# vireo.net
KiCad netlist of a schematic drawn in EAGLE
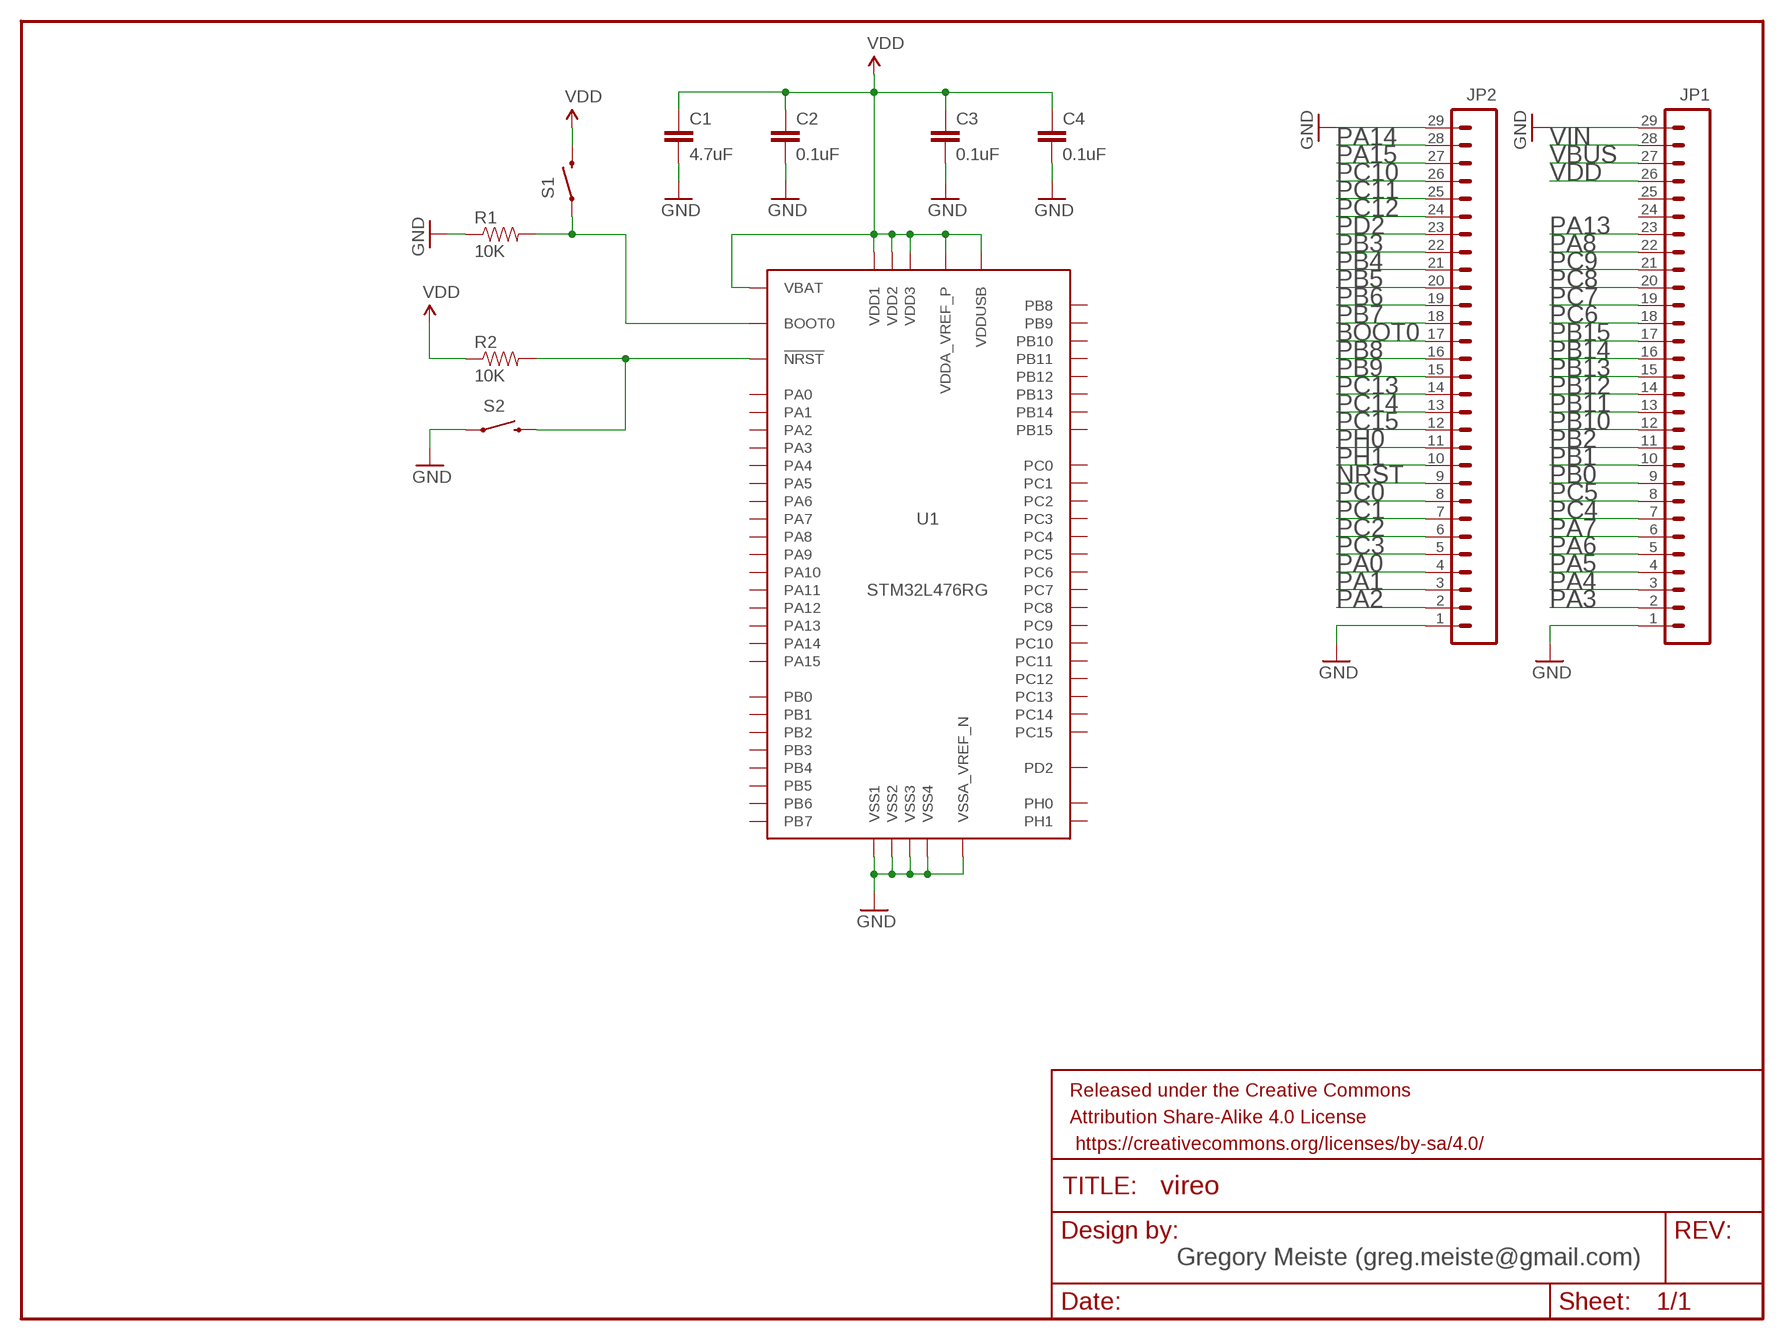
[diagram p0: schematic, sheet 1]

(export (version "E")
  (design (tool "Eeschema 10.0.6"))
  (components
    (comp (ref "C1")
      (value "4.7uF")
      (footprint "eagle-import:0603-CAP")
      (libsource (lib "eagle-import") (part "CAP0603-CAP"))
    )
    (comp (ref "C2")
      (value "0.1uF")
      (footprint "eagle-import:0603-CAP")
      (libsource (lib "eagle-import") (part "CAP0603-CAP"))
    )
    (comp (ref "C3")
      (value "0.1uF")
      (footprint "eagle-import:0603-CAP")
      (libsource (lib "eagle-import") (part "CAP0603-CAP"))
    )
    (comp (ref "C4")
      (value "0.1uF")
      (footprint "eagle-import:0603-CAP")
      (libsource (lib "eagle-import") (part "CAP0603-CAP"))
    )
    (comp (ref "FRAME1")
      (value "FRAME-LETTER")
      (footprint "eagle-import:CREATIVE_COMMONS")
      (libsource (lib "eagle-import") (part "FRAME-LETTER"))
    )
    (comp (ref "JP1")
      (value "M29NO_SILK")
      (footprint "eagle-import:1X29_NO_SILK")
      (libsource (lib "eagle-import") (part "M29NO_SILK"))
    )
    (comp (ref "JP2")
      (value "M29NO_SILK")
      (footprint "eagle-import:1X29_NO_SILK")
      (libsource (lib "eagle-import") (part "M29NO_SILK"))
    )
    (comp (ref "R1")
      (value "10K")
      (footprint "eagle-import:0603-RES")
      (libsource (lib "eagle-import") (part "RESISTOR0603-RES"))
    )
    (comp (ref "R2")
      (value "10K")
      (footprint "eagle-import:0603-RES")
      (libsource (lib "eagle-import") (part "RESISTOR0603-RES"))
    )
    (comp (ref "S1")
      (value "SWITCH-MOMENTARY-2SMD-3")
      (footprint "eagle-import:TACTILE_SWITCH_SMD-3")
      (libsource (lib "eagle-import") (part "SWITCH-MOMENTARY-2SMD-3"))
    )
    (comp (ref "S2")
      (value "SWITCH-MOMENTARY-2SMD-3")
      (footprint "eagle-import:TACTILE_SWITCH_SMD-3")
      (libsource (lib "eagle-import") (part "SWITCH-MOMENTARY-2SMD-3"))
    )
    (comp (ref "U1")
      (value "STM32L476RG")
      (footprint "eagle-import:LQFP64")
      (libsource (lib "eagle-import") (part "STM32L476RG"))
    )
  )
  (nets
    (net (code "1") (name "/BOOT0") (class "Default")
      (node (ref "JP2") (pin "17") (pinfunction "17_17") (pintype "passive"))
      (node (ref "R1") (pin "2") (pinfunction "2_2") (pintype "passive"))
      (node (ref "S1") (pin "1") (pinfunction "1_1") (pintype "passive"))
      (node (ref "U1") (pin "60") (pinfunction "BOOT0_60") (pintype "input"))
    )
    (net (code "2") (name "/NRST") (class "Default")
      (node (ref "JP2") (pin "9") (pinfunction "9_9") (pintype "passive"))
      (node (ref "R2") (pin "2") (pinfunction "2_2") (pintype "passive"))
      (node (ref "S2") (pin "4") (pinfunction "2_4") (pintype "passive"))
      (node (ref "U1") (pin "7") (pinfunction "~{NRST}_7") (pintype "input"))
    )
    (net (code "3") (name "/PA0") (class "Default")
      (node (ref "JP2") (pin "4") (pinfunction "4_4") (pintype "passive"))
    )
    (net (code "4") (name "/PA1") (class "Default")
      (node (ref "JP2") (pin "3") (pinfunction "3_3") (pintype "passive"))
    )
    (net (code "5") (name "/PA2") (class "Default")
      (node (ref "JP2") (pin "2") (pinfunction "2_2") (pintype "passive"))
    )
    (net (code "6") (name "/PA3") (class "Default")
      (node (ref "JP1") (pin "2") (pinfunction "2_2") (pintype "passive"))
    )
    (net (code "7") (name "/PA4") (class "Default")
      (node (ref "JP1") (pin "3") (pinfunction "3_3") (pintype "passive"))
    )
    (net (code "8") (name "/PA5") (class "Default")
      (node (ref "JP1") (pin "4") (pinfunction "4_4") (pintype "passive"))
    )
    (net (code "9") (name "/PA6") (class "Default")
      (node (ref "JP1") (pin "5") (pinfunction "5_5") (pintype "passive"))
    )
    (net (code "10") (name "/PA7") (class "Default")
      (node (ref "JP1") (pin "6") (pinfunction "6_6") (pintype "passive"))
    )
    (net (code "11") (name "/PA8") (class "Default")
      (node (ref "JP1") (pin "22") (pinfunction "22_22") (pintype "passive"))
    )
    (net (code "12") (name "/PA13") (class "Default")
      (node (ref "JP1") (pin "23") (pinfunction "23_23") (pintype "passive"))
    )
    (net (code "13") (name "/PA14") (class "Default")
      (node (ref "JP2") (pin "28") (pinfunction "28_28") (pintype "passive"))
    )
    (net (code "14") (name "/PA15") (class "Default")
      (node (ref "JP2") (pin "27") (pinfunction "27_27") (pintype "passive"))
    )
    (net (code "15") (name "/PB0") (class "Default")
      (node (ref "JP1") (pin "9") (pinfunction "9_9") (pintype "passive"))
    )
    (net (code "16") (name "/PB1") (class "Default")
      (node (ref "JP1") (pin "10") (pinfunction "10_10") (pintype "passive"))
    )
    (net (code "17") (name "/PB2") (class "Default")
      (node (ref "JP1") (pin "11") (pinfunction "11_11") (pintype "passive"))
    )
    (net (code "18") (name "/PB3") (class "Default")
      (node (ref "JP2") (pin "22") (pinfunction "22_22") (pintype "passive"))
    )
    (net (code "19") (name "/PB4") (class "Default")
      (node (ref "JP2") (pin "21") (pinfunction "21_21") (pintype "passive"))
    )
    (net (code "20") (name "/PB5") (class "Default")
      (node (ref "JP2") (pin "20") (pinfunction "20_20") (pintype "passive"))
    )
    (net (code "21") (name "/PB6") (class "Default")
      (node (ref "JP2") (pin "19") (pinfunction "19_19") (pintype "passive"))
    )
    (net (code "22") (name "/PB7") (class "Default")
      (node (ref "JP2") (pin "18") (pinfunction "18_18") (pintype "passive"))
    )
    (net (code "23") (name "/PB8") (class "Default")
      (node (ref "JP2") (pin "16") (pinfunction "16_16") (pintype "passive"))
    )
    (net (code "24") (name "/PB9") (class "Default")
      (node (ref "JP2") (pin "15") (pinfunction "15_15") (pintype "passive"))
    )
    (net (code "25") (name "/PB10") (class "Default")
      (node (ref "JP1") (pin "12") (pinfunction "12_12") (pintype "passive"))
    )
    (net (code "26") (name "/PB11") (class "Default")
      (node (ref "JP1") (pin "13") (pinfunction "13_13") (pintype "passive"))
    )
    (net (code "27") (name "/PB12") (class "Default")
      (node (ref "JP1") (pin "14") (pinfunction "14_14") (pintype "passive"))
    )
    (net (code "28") (name "/PB13") (class "Default")
      (node (ref "JP1") (pin "15") (pinfunction "15_15") (pintype "passive"))
    )
    (net (code "29") (name "/PB14") (class "Default")
      (node (ref "JP1") (pin "16") (pinfunction "16_16") (pintype "passive"))
    )
    (net (code "30") (name "/PB15") (class "Default")
      (node (ref "JP1") (pin "17") (pinfunction "17_17") (pintype "passive"))
    )
    (net (code "31") (name "/PC0") (class "Default")
      (node (ref "JP2") (pin "8") (pinfunction "8_8") (pintype "passive"))
    )
    (net (code "32") (name "/PC1") (class "Default")
      (node (ref "JP2") (pin "7") (pinfunction "7_7") (pintype "passive"))
    )
    (net (code "33") (name "/PC2") (class "Default")
      (node (ref "JP2") (pin "6") (pinfunction "6_6") (pintype "passive"))
    )
    (net (code "34") (name "/PC3") (class "Default")
      (node (ref "JP2") (pin "5") (pinfunction "5_5") (pintype "passive"))
    )
    (net (code "35") (name "/PC4") (class "Default")
      (node (ref "JP1") (pin "7") (pinfunction "7_7") (pintype "passive"))
    )
    (net (code "36") (name "/PC5") (class "Default")
      (node (ref "JP1") (pin "8") (pinfunction "8_8") (pintype "passive"))
    )
    (net (code "37") (name "/PC6") (class "Default")
      (node (ref "JP1") (pin "18") (pinfunction "18_18") (pintype "passive"))
    )
    (net (code "38") (name "/PC7") (class "Default")
      (node (ref "JP1") (pin "19") (pinfunction "19_19") (pintype "passive"))
    )
    (net (code "39") (name "/PC8") (class "Default")
      (node (ref "JP1") (pin "20") (pinfunction "20_20") (pintype "passive"))
    )
    (net (code "40") (name "/PC9") (class "Default")
      (node (ref "JP1") (pin "21") (pinfunction "21_21") (pintype "passive"))
    )
    (net (code "41") (name "/PC10") (class "Default")
      (node (ref "JP2") (pin "26") (pinfunction "26_26") (pintype "passive"))
    )
    (net (code "42") (name "/PC11") (class "Default")
      (node (ref "JP2") (pin "25") (pinfunction "25_25") (pintype "passive"))
    )
    (net (code "43") (name "/PC12") (class "Default")
      (node (ref "JP2") (pin "24") (pinfunction "24_24") (pintype "passive"))
    )
    (net (code "44") (name "/PC13") (class "Default")
      (node (ref "JP2") (pin "14") (pinfunction "14_14") (pintype "passive"))
    )
    (net (code "45") (name "/PC14") (class "Default")
      (node (ref "JP2") (pin "13") (pinfunction "13_13") (pintype "passive"))
    )
    (net (code "46") (name "/PC15") (class "Default")
      (node (ref "JP2") (pin "12") (pinfunction "12_12") (pintype "passive"))
    )
    (net (code "47") (name "/PD2") (class "Default")
      (node (ref "JP2") (pin "23") (pinfunction "23_23") (pintype "passive"))
    )
    (net (code "48") (name "/PH0") (class "Default")
      (node (ref "JP2") (pin "11") (pinfunction "11_11") (pintype "passive"))
    )
    (net (code "49") (name "/PH1") (class "Default")
      (node (ref "JP2") (pin "10") (pinfunction "10_10") (pintype "passive"))
    )
    (net (code "50") (name "/VBUS") (class "Default")
      (node (ref "JP1") (pin "27") (pinfunction "27_27") (pintype "passive"))
    )
    (net (code "51") (name "/VIN") (class "Default")
      (node (ref "JP1") (pin "28") (pinfunction "28_28") (pintype "passive"))
    )
    (net (code "52") (name "GND") (class "Default")
      (node (ref "C1") (pin "2") (pinfunction "2_2") (pintype "passive"))
      (node (ref "C2") (pin "2") (pinfunction "2_2") (pintype "passive"))
      (node (ref "C3") (pin "2") (pinfunction "2_2") (pintype "passive"))
      (node (ref "C4") (pin "2") (pinfunction "2_2") (pintype "passive"))
      (node (ref "JP1") (pin "1") (pinfunction "1_1") (pintype "passive"))
      (node (ref "JP1") (pin "29") (pinfunction "29_29") (pintype "passive"))
      (node (ref "JP2") (pin "1") (pinfunction "1_1") (pintype "passive"))
      (node (ref "JP2") (pin "29") (pinfunction "29_29") (pintype "passive"))
      (node (ref "R1") (pin "1") (pinfunction "1_1") (pintype "passive"))
      (node (ref "S2") (pin "1") (pinfunction "1_1") (pintype "passive"))
      (node (ref "U1") (pin "12") (pinfunction "VSSA_VREF_N_12") (pintype "power_in"))
      (node (ref "U1") (pin "18") (pinfunction "VSS1_18") (pintype "power_in"))
      (node (ref "U1") (pin "31") (pinfunction "VSS2_31") (pintype "power_in"))
      (node (ref "U1") (pin "47") (pinfunction "VSS3_47") (pintype "power_in"))
      (node (ref "U1") (pin "63") (pinfunction "VSS4_63") (pintype "power_in"))
    )
    (net (code "53") (name "VDD") (class "Default")
      (node (ref "C1") (pin "1") (pinfunction "1_1") (pintype "passive"))
      (node (ref "C2") (pin "1") (pinfunction "1_1") (pintype "passive"))
      (node (ref "C3") (pin "1") (pinfunction "1_1") (pintype "passive"))
      (node (ref "C4") (pin "1") (pinfunction "1_1") (pintype "passive"))
      (node (ref "JP1") (pin "26") (pinfunction "26_26") (pintype "passive"))
      (node (ref "R2") (pin "1") (pinfunction "1_1") (pintype "passive"))
      (node (ref "S1") (pin "4") (pinfunction "2_4") (pintype "passive"))
      (node (ref "U1") (pin "1") (pinfunction "VBAT_1") (pintype "power_in"))
      (node (ref "U1") (pin "13") (pinfunction "VDDA_VREF_P_13") (pintype "power_in"))
      (node (ref "U1") (pin "19") (pinfunction "VDD1_19") (pintype "power_in"))
      (node (ref "U1") (pin "32") (pinfunction "VDD2_32") (pintype "power_in"))
      (node (ref "U1") (pin "48") (pinfunction "VDDUSB_48") (pintype "power_in"))
      (node (ref "U1") (pin "64") (pinfunction "VDD3_64") (pintype "power_in"))
    )
    (net (code "54") (name "unconnected-(JP1-Pad24)") (class "Default")
      (node (ref "JP1") (pin "24") (pinfunction "24_24") (pintype "passive"))
    )
    (net (code "55") (name "unconnected-(JP1-Pad25)") (class "Default")
      (node (ref "JP1") (pin "25") (pinfunction "25_25") (pintype "passive"))
    )
    (net (code "56") (name "unconnected-(U1-PA0-Pad14)") (class "Default")
      (node (ref "U1") (pin "14") (pinfunction "PA0_14") (pintype "bidirectional"))
    )
    (net (code "57") (name "unconnected-(U1-PA1-Pad15)") (class "Default")
      (node (ref "U1") (pin "15") (pinfunction "PA1_15") (pintype "bidirectional"))
    )
    (net (code "58") (name "unconnected-(U1-PA2-Pad16)") (class "Default")
      (node (ref "U1") (pin "16") (pinfunction "PA2_16") (pintype "bidirectional"))
    )
    (net (code "59") (name "unconnected-(U1-PA3-Pad17)") (class "Default")
      (node (ref "U1") (pin "17") (pinfunction "PA3_17") (pintype "bidirectional"))
    )
    (net (code "60") (name "unconnected-(U1-PA4-Pad20)") (class "Default")
      (node (ref "U1") (pin "20") (pinfunction "PA4_20") (pintype "bidirectional"))
    )
    (net (code "61") (name "unconnected-(U1-PA5-Pad21)") (class "Default")
      (node (ref "U1") (pin "21") (pinfunction "PA5_21") (pintype "bidirectional"))
    )
    (net (code "62") (name "unconnected-(U1-PA6-Pad22)") (class "Default")
      (node (ref "U1") (pin "22") (pinfunction "PA6_22") (pintype "bidirectional"))
    )
    (net (code "63") (name "unconnected-(U1-PA7-Pad23)") (class "Default")
      (node (ref "U1") (pin "23") (pinfunction "PA7_23") (pintype "bidirectional"))
    )
    (net (code "64") (name "unconnected-(U1-PA8-Pad41)") (class "Default")
      (node (ref "U1") (pin "41") (pinfunction "PA8_41") (pintype "bidirectional"))
    )
    (net (code "65") (name "unconnected-(U1-PA9-Pad42)") (class "Default")
      (node (ref "U1") (pin "42") (pinfunction "PA9_42") (pintype "bidirectional"))
    )
    (net (code "66") (name "unconnected-(U1-PA10-Pad43)") (class "Default")
      (node (ref "U1") (pin "43") (pinfunction "PA10_43") (pintype "bidirectional"))
    )
    (net (code "67") (name "unconnected-(U1-PA11-Pad44)") (class "Default")
      (node (ref "U1") (pin "44") (pinfunction "PA11_44") (pintype "bidirectional"))
    )
    (net (code "68") (name "unconnected-(U1-PA12-Pad45)") (class "Default")
      (node (ref "U1") (pin "45") (pinfunction "PA12_45") (pintype "bidirectional"))
    )
    (net (code "69") (name "unconnected-(U1-PA13-Pad46)") (class "Default")
      (node (ref "U1") (pin "46") (pinfunction "PA13_46") (pintype "bidirectional"))
    )
    (net (code "70") (name "unconnected-(U1-PA14-Pad49)") (class "Default")
      (node (ref "U1") (pin "49") (pinfunction "PA14_49") (pintype "bidirectional"))
    )
    (net (code "71") (name "unconnected-(U1-PA15-Pad50)") (class "Default")
      (node (ref "U1") (pin "50") (pinfunction "PA15_50") (pintype "bidirectional"))
    )
    (net (code "72") (name "unconnected-(U1-PB0-Pad26)") (class "Default")
      (node (ref "U1") (pin "26") (pinfunction "PB0_26") (pintype "bidirectional"))
    )
    (net (code "73") (name "unconnected-(U1-PB1-Pad27)") (class "Default")
      (node (ref "U1") (pin "27") (pinfunction "PB1_27") (pintype "bidirectional"))
    )
    (net (code "74") (name "unconnected-(U1-PB2-Pad28)") (class "Default")
      (node (ref "U1") (pin "28") (pinfunction "PB2_28") (pintype "bidirectional"))
    )
    (net (code "75") (name "unconnected-(U1-PB3-Pad55)") (class "Default")
      (node (ref "U1") (pin "55") (pinfunction "PB3_55") (pintype "bidirectional"))
    )
    (net (code "76") (name "unconnected-(U1-PB4-Pad56)") (class "Default")
      (node (ref "U1") (pin "56") (pinfunction "PB4_56") (pintype "bidirectional"))
    )
    (net (code "77") (name "unconnected-(U1-PB5-Pad57)") (class "Default")
      (node (ref "U1") (pin "57") (pinfunction "PB5_57") (pintype "bidirectional"))
    )
    (net (code "78") (name "unconnected-(U1-PB6-Pad58)") (class "Default")
      (node (ref "U1") (pin "58") (pinfunction "PB6_58") (pintype "bidirectional"))
    )
    (net (code "79") (name "unconnected-(U1-PB7-Pad59)") (class "Default")
      (node (ref "U1") (pin "59") (pinfunction "PB7_59") (pintype "bidirectional"))
    )
    (net (code "80") (name "unconnected-(U1-PB8-Pad61)") (class "Default")
      (node (ref "U1") (pin "61") (pinfunction "PB8_61") (pintype "bidirectional"))
    )
    (net (code "81") (name "unconnected-(U1-PB9-Pad62)") (class "Default")
      (node (ref "U1") (pin "62") (pinfunction "PB9_62") (pintype "bidirectional"))
    )
    (net (code "82") (name "unconnected-(U1-PB10-Pad29)") (class "Default")
      (node (ref "U1") (pin "29") (pinfunction "PB10_29") (pintype "bidirectional"))
    )
    (net (code "83") (name "unconnected-(U1-PB11-Pad30)") (class "Default")
      (node (ref "U1") (pin "30") (pinfunction "PB11_30") (pintype "bidirectional"))
    )
    (net (code "84") (name "unconnected-(U1-PB12-Pad33)") (class "Default")
      (node (ref "U1") (pin "33") (pinfunction "PB12_33") (pintype "bidirectional"))
    )
    (net (code "85") (name "unconnected-(U1-PB13-Pad34)") (class "Default")
      (node (ref "U1") (pin "34") (pinfunction "PB13_34") (pintype "bidirectional"))
    )
    (net (code "86") (name "unconnected-(U1-PB14-Pad35)") (class "Default")
      (node (ref "U1") (pin "35") (pinfunction "PB14_35") (pintype "bidirectional"))
    )
    (net (code "87") (name "unconnected-(U1-PB15-Pad36)") (class "Default")
      (node (ref "U1") (pin "36") (pinfunction "PB15_36") (pintype "bidirectional"))
    )
    (net (code "88") (name "unconnected-(U1-PC0-Pad8)") (class "Default")
      (node (ref "U1") (pin "8") (pinfunction "PC0_8") (pintype "bidirectional"))
    )
    (net (code "89") (name "unconnected-(U1-PC1-Pad9)") (class "Default")
      (node (ref "U1") (pin "9") (pinfunction "PC1_9") (pintype "bidirectional"))
    )
    (net (code "90") (name "unconnected-(U1-PC2-Pad10)") (class "Default")
      (node (ref "U1") (pin "10") (pinfunction "PC2_10") (pintype "bidirectional"))
    )
    (net (code "91") (name "unconnected-(U1-PC3-Pad11)") (class "Default")
      (node (ref "U1") (pin "11") (pinfunction "PC3_11") (pintype "bidirectional"))
    )
    (net (code "92") (name "unconnected-(U1-PC4-Pad24)") (class "Default")
      (node (ref "U1") (pin "24") (pinfunction "PC4_24") (pintype "bidirectional"))
    )
    (net (code "93") (name "unconnected-(U1-PC5-Pad25)") (class "Default")
      (node (ref "U1") (pin "25") (pinfunction "PC5_25") (pintype "bidirectional"))
    )
    (net (code "94") (name "unconnected-(U1-PC6-Pad37)") (class "Default")
      (node (ref "U1") (pin "37") (pinfunction "PC6_37") (pintype "bidirectional"))
    )
    (net (code "95") (name "unconnected-(U1-PC7-Pad38)") (class "Default")
      (node (ref "U1") (pin "38") (pinfunction "PC7_38") (pintype "bidirectional"))
    )
    (net (code "96") (name "unconnected-(U1-PC8-Pad39)") (class "Default")
      (node (ref "U1") (pin "39") (pinfunction "PC8_39") (pintype "bidirectional"))
    )
    (net (code "97") (name "unconnected-(U1-PC9-Pad40)") (class "Default")
      (node (ref "U1") (pin "40") (pinfunction "PC9_40") (pintype "bidirectional"))
    )
    (net (code "98") (name "unconnected-(U1-PC10-Pad51)") (class "Default")
      (node (ref "U1") (pin "51") (pinfunction "PC10_51") (pintype "bidirectional"))
    )
    (net (code "99") (name "unconnected-(U1-PC11-Pad52)") (class "Default")
      (node (ref "U1") (pin "52") (pinfunction "PC11_52") (pintype "bidirectional"))
    )
    (net (code "100") (name "unconnected-(U1-PC12-Pad53)") (class "Default")
      (node (ref "U1") (pin "53") (pinfunction "PC12_53") (pintype "bidirectional"))
    )
    (net (code "101") (name "unconnected-(U1-PC13-Pad2)") (class "Default")
      (node (ref "U1") (pin "2") (pinfunction "PC13_2") (pintype "bidirectional"))
    )
    (net (code "102") (name "unconnected-(U1-PC14-Pad3)") (class "Default")
      (node (ref "U1") (pin "3") (pinfunction "PC14_3") (pintype "bidirectional"))
    )
    (net (code "103") (name "unconnected-(U1-PC15-Pad4)") (class "Default")
      (node (ref "U1") (pin "4") (pinfunction "PC15_4") (pintype "bidirectional"))
    )
    (net (code "104") (name "unconnected-(U1-PD2-Pad54)") (class "Default")
      (node (ref "U1") (pin "54") (pinfunction "PD2_54") (pintype "bidirectional"))
    )
    (net (code "105") (name "unconnected-(U1-PH0-Pad5)") (class "Default")
      (node (ref "U1") (pin "5") (pinfunction "PH0_5") (pintype "bidirectional"))
    )
    (net (code "106") (name "unconnected-(U1-PH1-Pad6)") (class "Default")
      (node (ref "U1") (pin "6") (pinfunction "PH1_6") (pintype "bidirectional"))
    )
  )
)
